# MotorControl.net
KiCad netlist of a schematic drawn in Altium Designer
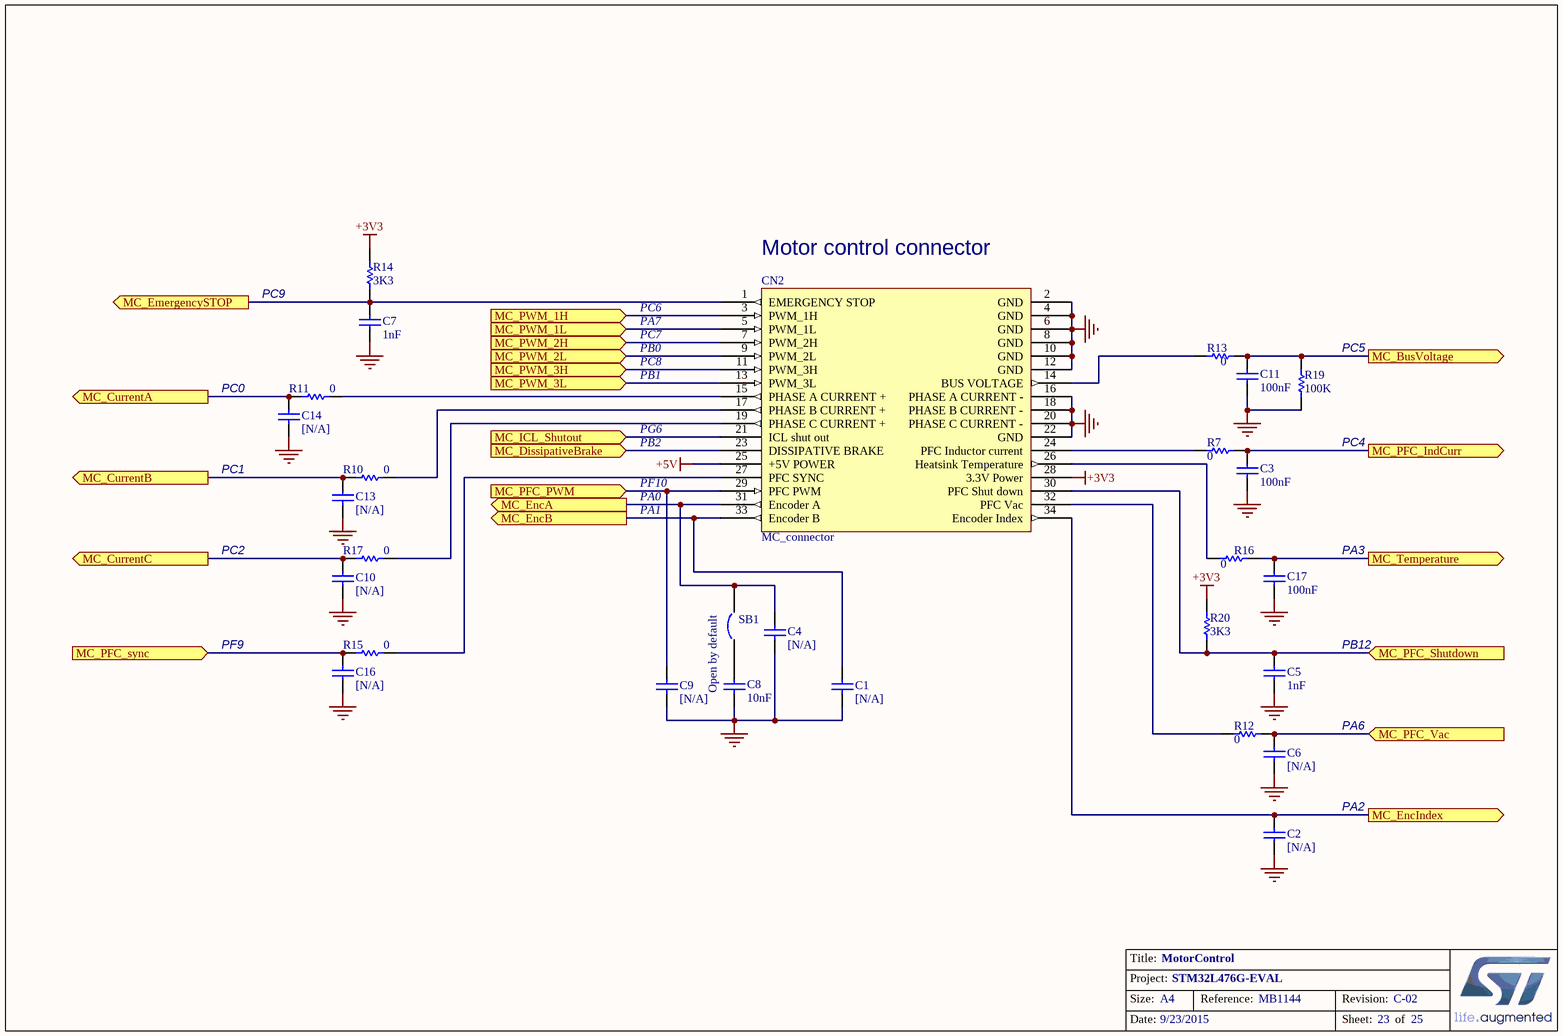
[diagram p0: MotorControl.SchDoc]

(export (version "E")
  (design (tool "Eeschema 10.0.6"))
  (components
    (comp (ref "C1")
      (value "[N/A]")
      (footprint "0603C")
      (description "Capacitor")
      (fields (field (name "PUBLISHER") "Altium Limited"))
      (libsource (lib "Miscellaneous Devices") (part "cap"))
    )
    (comp (ref "C2")
      (value "[N/A]")
      (footprint "0603C")
      (description "Capacitor")
      (fields (field (name "PUBLISHER") "Altium Limited"))
      (libsource (lib "Miscellaneous Devices") (part "cap"))
    )
    (comp (ref "C3")
      (value "100nF")
      (footprint "0402C")
      (description "Capacitor")
      (fields (field (name "PUBLISHER") "Altium Limited"))
      (libsource (lib "Miscellaneous Devices") (part "Cap"))
    )
    (comp (ref "C4")
      (value "[N/A]")
      (footprint "0603C")
      (description "Capacitor")
      (fields (field (name "PUBLISHER") "Altium Limited"))
      (libsource (lib "Miscellaneous Devices") (part "cap"))
    )
    (comp (ref "C5")
      (value "1nF")
      (footprint "0402C")
      (description "Capacitor")
      (fields (field (name "PUBLISHER") "Altium Limited"))
      (libsource (lib "Miscellaneous Devices") (part "CAP"))
    )
    (comp (ref "C6")
      (value "[N/A]")
      (footprint "0603C")
      (description "Capacitor")
      (fields (field (name "PUBLISHER") "Altium Limited"))
      (libsource (lib "Miscellaneous Devices") (part "cap"))
    )
    (comp (ref "C7")
      (value "1nF")
      (footprint "0402C")
      (description "Capacitor")
      (fields (field (name "PUBLISHER") "Altium Limited"))
      (libsource (lib "Miscellaneous Devices") (part "CAP"))
    )
    (comp (ref "C8")
      (value "10nF")
      (footprint "0402C")
      (description "Capacitor")
      (fields (field (name "PUBLISHER") "Altium Limited"))
      (libsource (lib "Miscellaneous Devices") (part "CAP"))
    )
    (comp (ref "C9")
      (value "[N/A]")
      (footprint "0603C")
      (description "Capacitor")
      (fields (field (name "PUBLISHER") "Altium Limited"))
      (libsource (lib "Miscellaneous Devices") (part "cap"))
    )
    (comp (ref "C10")
      (value "[N/A]")
      (footprint "0603C")
      (description "Capacitor")
      (fields (field (name "PUBLISHER") "Altium Limited"))
      (libsource (lib "Miscellaneous Devices") (part "cap"))
    )
    (comp (ref "C11")
      (value "100nF")
      (footprint "0402C")
      (description "Capacitor")
      (fields (field (name "PUBLISHER") "Altium Limited"))
      (libsource (lib "Miscellaneous Devices") (part "Cap"))
    )
    (comp (ref "C13")
      (value "[N/A]")
      (footprint "0603C")
      (description "Capacitor")
      (fields (field (name "PUBLISHER") "Altium Limited"))
      (libsource (lib "Miscellaneous Devices") (part "cap"))
    )
    (comp (ref "C14")
      (value "[N/A]")
      (footprint "0603C")
      (description "Capacitor")
      (fields (field (name "PUBLISHER") "Altium Limited"))
      (libsource (lib "Miscellaneous Devices") (part "cap"))
    )
    (comp (ref "C16")
      (value "[N/A]")
      (footprint "0603C")
      (description "Capacitor")
      (fields (field (name "PUBLISHER") "Altium Limited"))
      (libsource (lib "Miscellaneous Devices") (part "cap"))
    )
    (comp (ref "C17")
      (value "100nF")
      (footprint "0402C")
      (description "Capacitor")
      (fields (field (name "PUBLISHER") "Altium Limited"))
      (libsource (lib "Miscellaneous Devices") (part "Cap"))
    )
    (comp (ref "CN2")
      (value "MC_connector")
      (footprint "IDC34S")
      (libsource (lib "MB1019") (part "MC_connector_1"))
    )
    (comp (ref "R7")
      (value "0")
      (footprint "0603R")
      (description "Resistor")
      (fields (field (name "PUBLISHER") "Altium Limited"))
      (libsource (lib "Miscellaneous Devices") (part "Res1"))
    )
    (comp (ref "R10")
      (value "0")
      (footprint "0603R")
      (description "Resistor")
      (fields (field (name "PUBLISHER") "Altium Limited"))
      (libsource (lib "Miscellaneous Devices") (part "Res1"))
    )
    (comp (ref "R11")
      (value "0")
      (footprint "0603R")
      (description "Resistor")
      (fields (field (name "PUBLISHER") "Altium Limited"))
      (libsource (lib "Miscellaneous Devices") (part "Res1"))
    )
    (comp (ref "R12")
      (value "0")
      (footprint "0603R")
      (description "Resistor")
      (fields (field (name "PUBLISHER") "Altium Limited"))
      (libsource (lib "Miscellaneous Devices") (part "Res1"))
    )
    (comp (ref "R13")
      (value "0")
      (footprint "0603R")
      (description "Resistor")
      (fields (field (name "PUBLISHER") "Altium Limited"))
      (libsource (lib "Miscellaneous Devices") (part "Res1"))
    )
    (comp (ref "R14")
      (value "3K3")
      (footprint "0402R")
      (description "Resistor")
      (fields (field (name "PUBLISHER") "Altium Limited"))
      (libsource (lib "Miscellaneous Devices") (part "Res1"))
    )
    (comp (ref "R15")
      (value "0")
      (footprint "0603R")
      (description "Resistor")
      (fields (field (name "PUBLISHER") "Altium Limited"))
      (libsource (lib "Miscellaneous Devices") (part "Res1"))
    )
    (comp (ref "R16")
      (value "0")
      (footprint "0603R")
      (description "Resistor")
      (fields (field (name "PUBLISHER") "Altium Limited"))
      (libsource (lib "Miscellaneous Devices") (part "Res1"))
    )
    (comp (ref "R17")
      (value "0")
      (footprint "0603R")
      (description "Resistor")
      (fields (field (name "PUBLISHER") "Altium Limited"))
      (libsource (lib "Miscellaneous Devices") (part "Res1"))
    )
    (comp (ref "R19")
      (value "100K")
      (footprint "0402R")
      (description "Resistor")
      (fields (field (name "PUBLISHER") "Altium Limited"))
      (libsource (lib "Miscellaneous Devices") (part "res1"))
    )
    (comp (ref "R20")
      (value "3K3")
      (footprint "0402R")
      (description "Resistor")
      (fields (field (name "PUBLISHER") "Altium Limited"))
      (libsource (lib "Miscellaneous Devices") (part "Res1"))
    )
    (comp (ref "SB1")
      (value "Open by default")
      (footprint "SB_0603")
      (description "Circuit Breaker")
      (fields (field (name "PUBLISHER") "Altium Limited"))
      (libsource (lib "Miscellaneous Devices") (part "Circuit Breaker"))
    )
  )
  (nets
    (net (code "1") (name "+3V3") (class "Default")
      (node (ref "CN2") (pin "28") (pinfunction "3.3V_Power_28") (pintype "power_in"))
      (node (ref "R14") (pin "2") (pinfunction "2_2") (pintype "passive"))
      (node (ref "R20") (pin "2") (pinfunction "2_2") (pintype "passive"))
    )
    (net (code "2") (name "+5V") (class "Default")
      (node (ref "CN2") (pin "25") (pinfunction "+5V_POWER_25") (pintype "power_in"))
    )
    (net (code "3") (name "/MC_BusVoltage") (class "Default")
      (node (ref "C11") (pin "1") (pinfunction "1_1") (pintype "passive"))
      (node (ref "R13") (pin "2") (pinfunction "2_2") (pintype "passive"))
      (node (ref "R19") (pin "1") (pinfunction "1_1") (pintype "passive"))
    )
    (net (code "4") (name "/MC_CurrentA") (class "Default")
      (node (ref "C14") (pin "2") (pinfunction "2_2") (pintype "passive"))
      (node (ref "R11") (pin "1") (pinfunction "1_1") (pintype "passive"))
    )
    (net (code "5") (name "/MC_CurrentB") (class "Default")
      (node (ref "C13") (pin "2") (pinfunction "2_2") (pintype "passive"))
      (node (ref "R10") (pin "1") (pinfunction "1_1") (pintype "passive"))
    )
    (net (code "6") (name "/MC_CurrentC") (class "Default")
      (node (ref "C10") (pin "2") (pinfunction "2_2") (pintype "passive"))
      (node (ref "R17") (pin "1") (pinfunction "1_1") (pintype "passive"))
    )
    (net (code "7") (name "/MC_DissipativeBrake") (class "Default")
      (node (ref "CN2") (pin "23") (pinfunction "DISSIPATIVE_BRAKE_23") (pintype "passive"))
    )
    (net (code "8") (name "/MC_EmergencySTOP") (class "Default")
      (node (ref "C7") (pin "2") (pinfunction "2_2") (pintype "passive"))
      (node (ref "CN2") (pin "1") (pinfunction "EMERGENCY_STOP_1") (pintype "output"))
      (node (ref "R14") (pin "1") (pinfunction "1_1") (pintype "passive"))
    )
    (net (code "9") (name "/MC_EncA") (class "Default")
      (node (ref "C4") (pin "2") (pinfunction "2_2") (pintype "passive"))
      (node (ref "CN2") (pin "31") (pinfunction "Encoder_A_31") (pintype "output"))
      (node (ref "SB1") (pin "2") (pinfunction "2_2") (pintype "passive"))
    )
    (net (code "10") (name "/MC_EncB") (class "Default")
      (node (ref "C1") (pin "2") (pinfunction "2_2") (pintype "passive"))
      (node (ref "CN2") (pin "33") (pinfunction "Encoder_B_33") (pintype "output"))
    )
    (net (code "11") (name "/MC_EncIndex") (class "Default")
      (node (ref "C2") (pin "2") (pinfunction "2_2") (pintype "passive"))
      (node (ref "CN2") (pin "34") (pinfunction "Encoder_Index_34") (pintype "output"))
    )
    (net (code "12") (name "/MC_ICL_Shutout") (class "Default")
      (node (ref "CN2") (pin "21") (pinfunction "ICL_shut_out_21") (pintype "passive"))
    )
    (net (code "13") (name "/MC_PFC_IndCurr") (class "Default")
      (node (ref "C3") (pin "1") (pinfunction "1_1") (pintype "passive"))
      (node (ref "R7") (pin "2") (pinfunction "2_2") (pintype "passive"))
    )
    (net (code "14") (name "/MC_PFC_PWM") (class "Default")
      (node (ref "C9") (pin "2") (pinfunction "2_2") (pintype "passive"))
      (node (ref "CN2") (pin "29") (pinfunction "PFC_PWM_29") (pintype "input"))
    )
    (net (code "15") (name "/MC_PFC_Shutdown") (class "Default")
      (node (ref "C5") (pin "2") (pinfunction "2_2") (pintype "passive"))
      (node (ref "CN2") (pin "30") (pinfunction "PFC_Shut_down_30") (pintype "passive"))
      (node (ref "R20") (pin "1") (pinfunction "1_1") (pintype "passive"))
    )
    (net (code "16") (name "/MC_PFC_Vac") (class "Default")
      (node (ref "C6") (pin "2") (pinfunction "2_2") (pintype "passive"))
      (node (ref "R12") (pin "2") (pinfunction "2_2") (pintype "passive"))
    )
    (net (code "17") (name "/MC_PFC_sync") (class "Default")
      (node (ref "C16") (pin "2") (pinfunction "2_2") (pintype "passive"))
      (node (ref "R15") (pin "1") (pinfunction "1_1") (pintype "passive"))
    )
    (net (code "18") (name "/MC_PWM_1H") (class "Default")
      (node (ref "CN2") (pin "3") (pinfunction "PWM_1H_3") (pintype "input"))
    )
    (net (code "19") (name "/MC_PWM_1L") (class "Default")
      (node (ref "CN2") (pin "5") (pinfunction "PWM_1L_5") (pintype "input"))
    )
    (net (code "20") (name "/MC_PWM_2H") (class "Default")
      (node (ref "CN2") (pin "7") (pinfunction "PWM_2H_7") (pintype "input"))
    )
    (net (code "21") (name "/MC_PWM_2L") (class "Default")
      (node (ref "CN2") (pin "9") (pinfunction "PWM_2L_9") (pintype "input"))
    )
    (net (code "22") (name "/MC_PWM_3H") (class "Default")
      (node (ref "CN2") (pin "11") (pinfunction "PWM_3H_11") (pintype "input"))
    )
    (net (code "23") (name "/MC_PWM_3L") (class "Default")
      (node (ref "CN2") (pin "13") (pinfunction "PWM_3L_13") (pintype "input"))
    )
    (net (code "24") (name "/MC_Temperature") (class "Default")
      (node (ref "C17") (pin "1") (pinfunction "1_1") (pintype "passive"))
      (node (ref "R16") (pin "2") (pinfunction "2_2") (pintype "passive"))
    )
    (net (code "25") (name "GND") (class "Default")
      (node (ref "C1") (pin "1") (pinfunction "1_1") (pintype "passive"))
      (node (ref "C10") (pin "1") (pinfunction "1_1") (pintype "passive"))
      (node (ref "C11") (pin "2") (pinfunction "2_2") (pintype "passive"))
      (node (ref "C13") (pin "1") (pinfunction "1_1") (pintype "passive"))
      (node (ref "C14") (pin "1") (pinfunction "1_1") (pintype "passive"))
      (node (ref "C16") (pin "1") (pinfunction "1_1") (pintype "passive"))
      (node (ref "C17") (pin "2") (pinfunction "2_2") (pintype "passive"))
      (node (ref "C2") (pin "1") (pinfunction "1_1") (pintype "passive"))
      (node (ref "C3") (pin "2") (pinfunction "2_2") (pintype "passive"))
      (node (ref "C4") (pin "1") (pinfunction "1_1") (pintype "passive"))
      (node (ref "C5") (pin "1") (pinfunction "1_1") (pintype "passive"))
      (node (ref "C6") (pin "1") (pinfunction "1_1") (pintype "passive"))
      (node (ref "C7") (pin "1") (pinfunction "1_1") (pintype "passive"))
      (node (ref "C8") (pin "2") (pinfunction "2_2") (pintype "passive"))
      (node (ref "C9") (pin "1") (pinfunction "1_1") (pintype "passive"))
      (node (ref "CN2") (pin "10") (pinfunction "GND_10") (pintype "power_in"))
      (node (ref "CN2") (pin "12") (pinfunction "GND_12") (pintype "power_in"))
      (node (ref "CN2") (pin "16") (pinfunction "PHASE_A_CURRENT_-_16") (pintype "power_in"))
      (node (ref "CN2") (pin "18") (pinfunction "PHASE_B_CURRENT_-_18") (pintype "power_in"))
      (node (ref "CN2") (pin "2") (pinfunction "GND_2") (pintype "power_in"))
      (node (ref "CN2") (pin "20") (pinfunction "PHASE_C_CURRENT_-_20") (pintype "power_in"))
      (node (ref "CN2") (pin "22") (pinfunction "GND_22") (pintype "power_in"))
      (node (ref "CN2") (pin "4") (pinfunction "GND_4") (pintype "power_in"))
      (node (ref "CN2") (pin "6") (pinfunction "GND_6") (pintype "power_in"))
      (node (ref "CN2") (pin "8") (pinfunction "GND_8") (pintype "power_in"))
      (node (ref "R19") (pin "2") (pinfunction "2_2") (pintype "passive"))
    )
    (net (code "26") (name "Net-(C8-Pad1)") (class "Default")
      (node (ref "C8") (pin "1") (pinfunction "1_1") (pintype "passive"))
      (node (ref "SB1") (pin "1") (pinfunction "1_1") (pintype "passive"))
    )
    (net (code "27") (name "Net-(CN2-BUS_VOLTAGE)") (class "Default")
      (node (ref "CN2") (pin "14") (pinfunction "BUS_VOLTAGE_14") (pintype "output"))
      (node (ref "R13") (pin "1") (pinfunction "1_1") (pintype "passive"))
    )
    (net (code "28") (name "Net-(CN2-Heatsink_Temperature)") (class "Default")
      (node (ref "CN2") (pin "26") (pinfunction "Heatsink_Temperature_26") (pintype "output"))
      (node (ref "R16") (pin "1") (pinfunction "1_1") (pintype "passive"))
    )
    (net (code "29") (name "Net-(CN2-PFC_Inductor_current)") (class "Default")
      (node (ref "CN2") (pin "24") (pinfunction "PFC_Inductor_current_24") (pintype "passive"))
      (node (ref "R7") (pin "1") (pinfunction "1_1") (pintype "passive"))
    )
    (net (code "30") (name "Net-(CN2-PFC_SYNC)") (class "Default")
      (node (ref "CN2") (pin "27") (pinfunction "PFC_SYNC_27") (pintype "passive"))
      (node (ref "R15") (pin "2") (pinfunction "2_2") (pintype "passive"))
    )
    (net (code "31") (name "Net-(CN2-PFC_Vac)") (class "Default")
      (node (ref "CN2") (pin "32") (pinfunction "PFC_Vac_32") (pintype "passive"))
      (node (ref "R12") (pin "1") (pinfunction "1_1") (pintype "passive"))
    )
    (net (code "32") (name "Net-(CN2-PHASE_A_CURRENT_+)") (class "Default")
      (node (ref "CN2") (pin "15") (pinfunction "PHASE_A_CURRENT_+_15") (pintype "output"))
      (node (ref "R11") (pin "2") (pinfunction "2_2") (pintype "passive"))
    )
    (net (code "33") (name "Net-(CN2-PHASE_B_CURRENT_+)") (class "Default")
      (node (ref "CN2") (pin "17") (pinfunction "PHASE_B_CURRENT_+_17") (pintype "output"))
      (node (ref "R10") (pin "2") (pinfunction "2_2") (pintype "passive"))
    )
    (net (code "34") (name "Net-(CN2-PHASE_C_CURRENT_+)") (class "Default")
      (node (ref "CN2") (pin "19") (pinfunction "PHASE_C_CURRENT_+_19") (pintype "output"))
      (node (ref "R17") (pin "2") (pinfunction "2_2") (pintype "passive"))
    )
  )
)
